# Digital_Temperature_Sensor_Breakout_-_TM.net
KiCad netlist of a schematic drawn in EAGLE
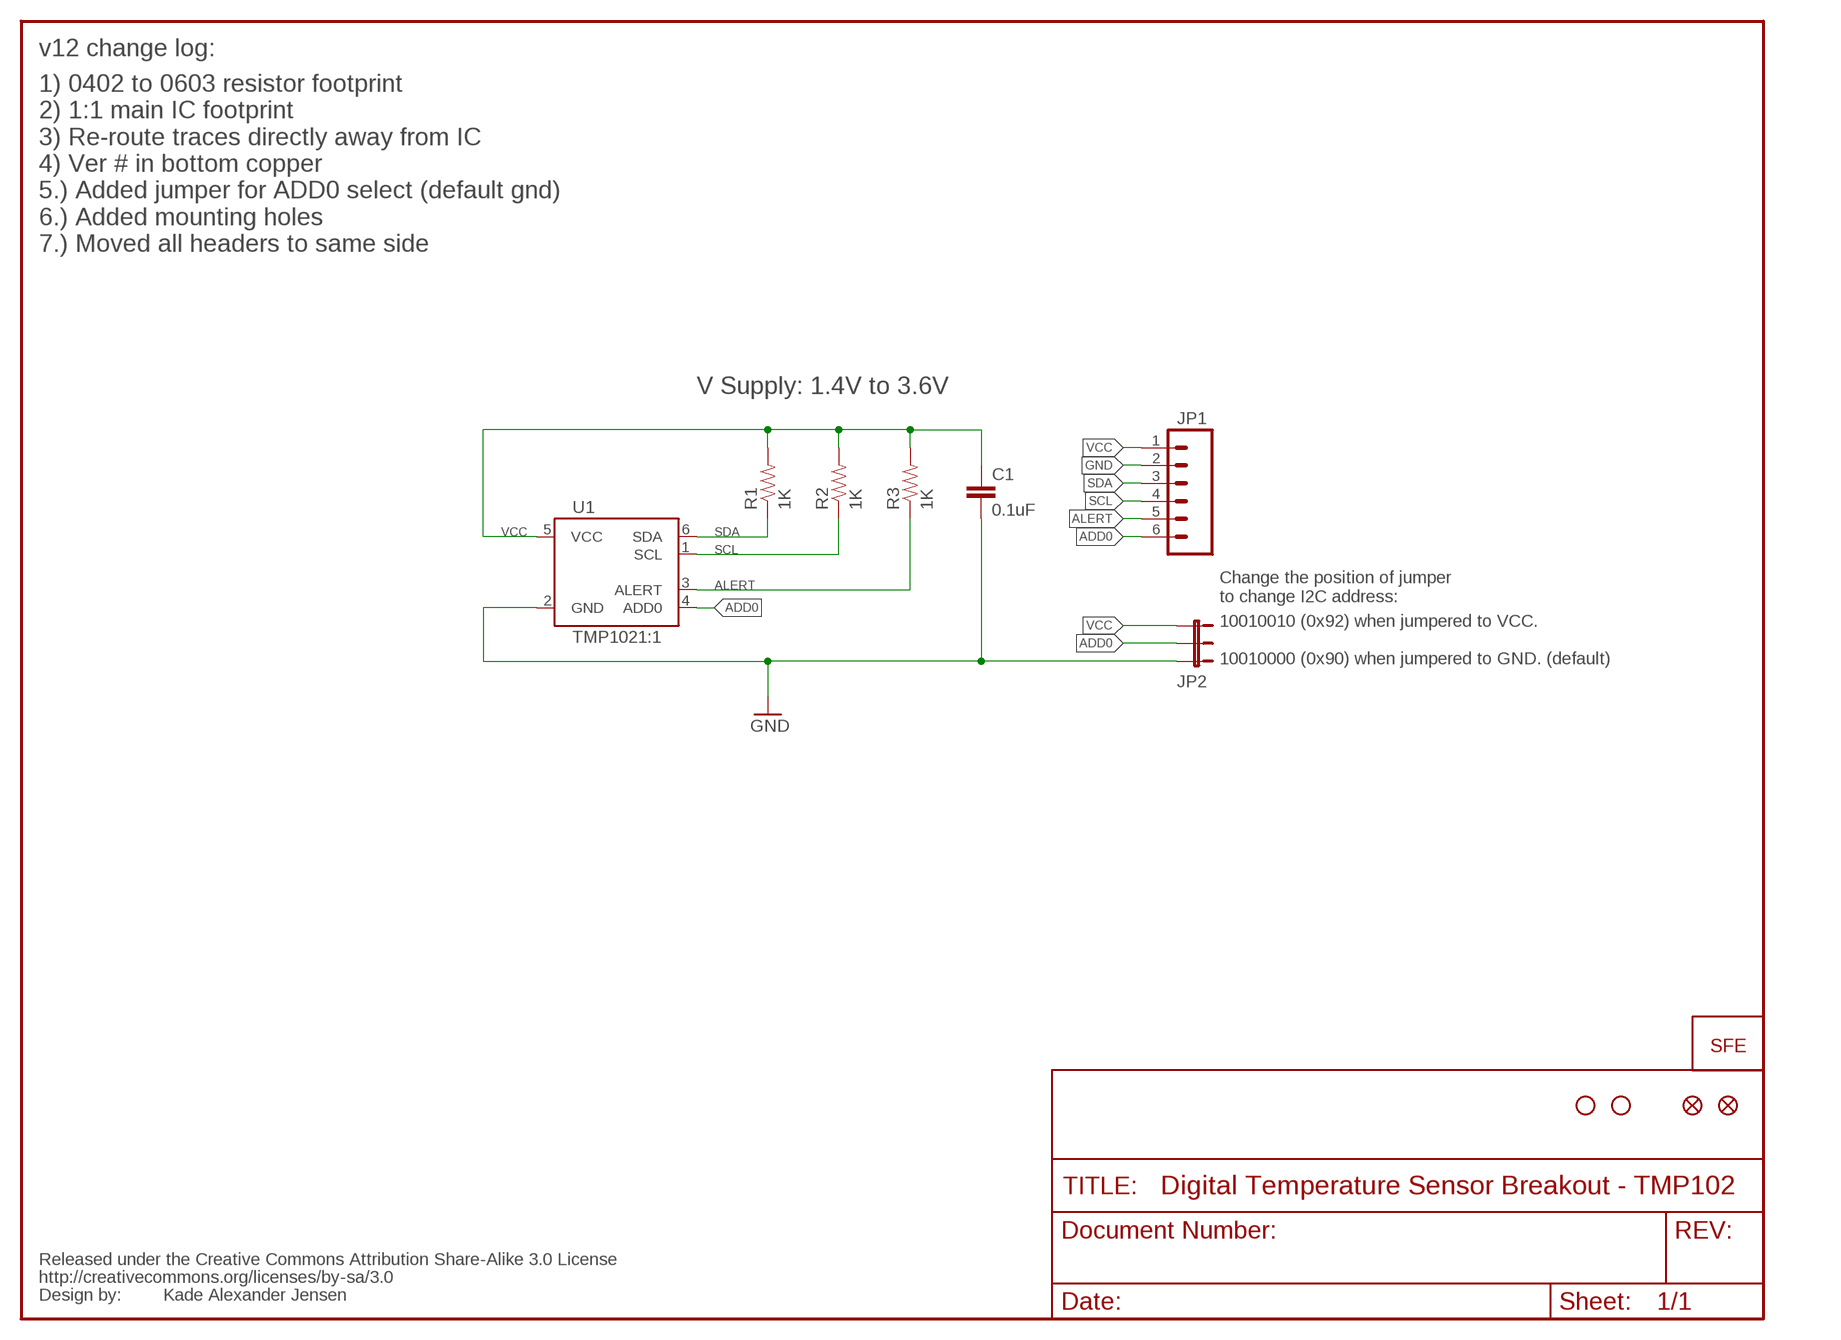
[diagram p0: schematic, sheet 1]

(export (version "E")
  (design (tool "Eeschema 10.0.6"))
  (components
    (comp (ref "C1")
      (value "0.1uF")
      (footprint "eagle-import:0603-CAP")
      (libsource (lib "eagle-import") (part "CAP0603-CAP"))
    )
    (comp (ref "JP1")
      (value "M06SIP")
      (footprint "eagle-import:1X06")
      (libsource (lib "eagle-import") (part "M06SIP"))
    )
    (comp (ref "JP2")
      (value "JUMPER-32-3")
      (footprint "eagle-import:SJ_3_PASTE2&3")
      (libsource (lib "eagle-import") (part "JUMPER-32-3"))
    )
    (comp (ref "JP3")
      (value "LOGO-SFESK")
      (footprint "eagle-import:SFE-LOGO-FLAME")
      (libsource (lib "eagle-import") (part "LOGO-SFESK"))
    )
    (comp (ref "JP4")
      (value "FIDUCIAL1X2")
      (footprint "eagle-import:FIDUCIAL-1X2")
      (libsource (lib "eagle-import") (part "FIDUCIAL1X2"))
    )
    (comp (ref "JP5")
      (value "FIDUCIAL1X2")
      (footprint "eagle-import:FIDUCIAL-1X2")
      (libsource (lib "eagle-import") (part "FIDUCIAL1X2"))
    )
    (comp (ref "JP6")
      (value "STAND-OFFTIGHT")
      (footprint "eagle-import:STAND-OFF-TIGHT")
      (libsource (lib "eagle-import") (part "STAND-OFFTIGHT"))
    )
    (comp (ref "JP7")
      (value "STAND-OFFTIGHT")
      (footprint "eagle-import:STAND-OFF-TIGHT")
      (libsource (lib "eagle-import") (part "STAND-OFFTIGHT"))
    )
    (comp (ref "R1")
      (value "1K")
      (footprint "eagle-import:0603-RES")
      (libsource (lib "eagle-import") (part "RESISTOR0603-RES"))
    )
    (comp (ref "R2")
      (value "1K")
      (footprint "eagle-import:0603-RES")
      (libsource (lib "eagle-import") (part "RESISTOR0603-RES"))
    )
    (comp (ref "R3")
      (value "1K")
      (footprint "eagle-import:0603-RES")
      (libsource (lib "eagle-import") (part "RESISTOR0603-RES"))
    )
    (comp (ref "U$2")
      (value "CREATIVE_COMMONS")
      (footprint "eagle-import:CREATIVE_COMMONS")
      (libsource (lib "eagle-import") (part "CREATIVE_COMMONS"))
    )
    (comp (ref "U1")
      (value "TMP1021:1")
      (footprint "eagle-import:SOT563-2")
      (libsource (lib "eagle-import") (part "TMP1021{colon}1"))
    )
  )
  (nets
    (net (code "1") (name "ADD0") (class "Default")
      (node (ref "JP1") (pin "6") (pinfunction "6_6") (pintype "passive"))
      (node (ref "JP2") (pin "2") (pinfunction "2_2") (pintype "passive"))
      (node (ref "U1") (pin "4") (pinfunction "ADD0_4") (pintype "bidirectional"))
    )
    (net (code "2") (name "ALERT") (class "Default")
      (node (ref "JP1") (pin "5") (pinfunction "5_5") (pintype "passive"))
      (node (ref "R3") (pin "1") (pinfunction "1_1") (pintype "passive"))
      (node (ref "U1") (pin "3") (pinfunction "ALERT_3") (pintype "bidirectional"))
    )
    (net (code "3") (name "GND") (class "Default")
      (node (ref "C1") (pin "2") (pinfunction "2_2") (pintype "passive"))
      (node (ref "JP1") (pin "2") (pinfunction "2_2") (pintype "passive"))
      (node (ref "JP2") (pin "3") (pinfunction "3_3") (pintype "passive"))
      (node (ref "U1") (pin "2") (pinfunction "GND_2") (pintype "bidirectional"))
    )
    (net (code "4") (name "SCL") (class "Default")
      (node (ref "JP1") (pin "4") (pinfunction "4_4") (pintype "passive"))
      (node (ref "R2") (pin "1") (pinfunction "1_1") (pintype "passive"))
      (node (ref "U1") (pin "1") (pinfunction "SCL_1") (pintype "bidirectional"))
    )
    (net (code "5") (name "SDA") (class "Default")
      (node (ref "JP1") (pin "3") (pinfunction "3_3") (pintype "passive"))
      (node (ref "R1") (pin "1") (pinfunction "1_1") (pintype "passive"))
      (node (ref "U1") (pin "6") (pinfunction "SDA_6") (pintype "bidirectional"))
    )
    (net (code "6") (name "VCC") (class "Default")
      (node (ref "C1") (pin "1") (pinfunction "1_1") (pintype "passive"))
      (node (ref "JP1") (pin "1") (pinfunction "1_1") (pintype "passive"))
      (node (ref "JP2") (pin "1") (pinfunction "1_1") (pintype "passive"))
      (node (ref "R1") (pin "2") (pinfunction "2_2") (pintype "passive"))
      (node (ref "R2") (pin "2") (pinfunction "2_2") (pintype "passive"))
      (node (ref "R3") (pin "2") (pinfunction "2_2") (pintype "passive"))
      (node (ref "U1") (pin "5") (pinfunction "VCC_5") (pintype "bidirectional"))
    )
  )
)
